# ProPrj.net
KiCad netlist of a schematic drawn in EasyEDA Pro
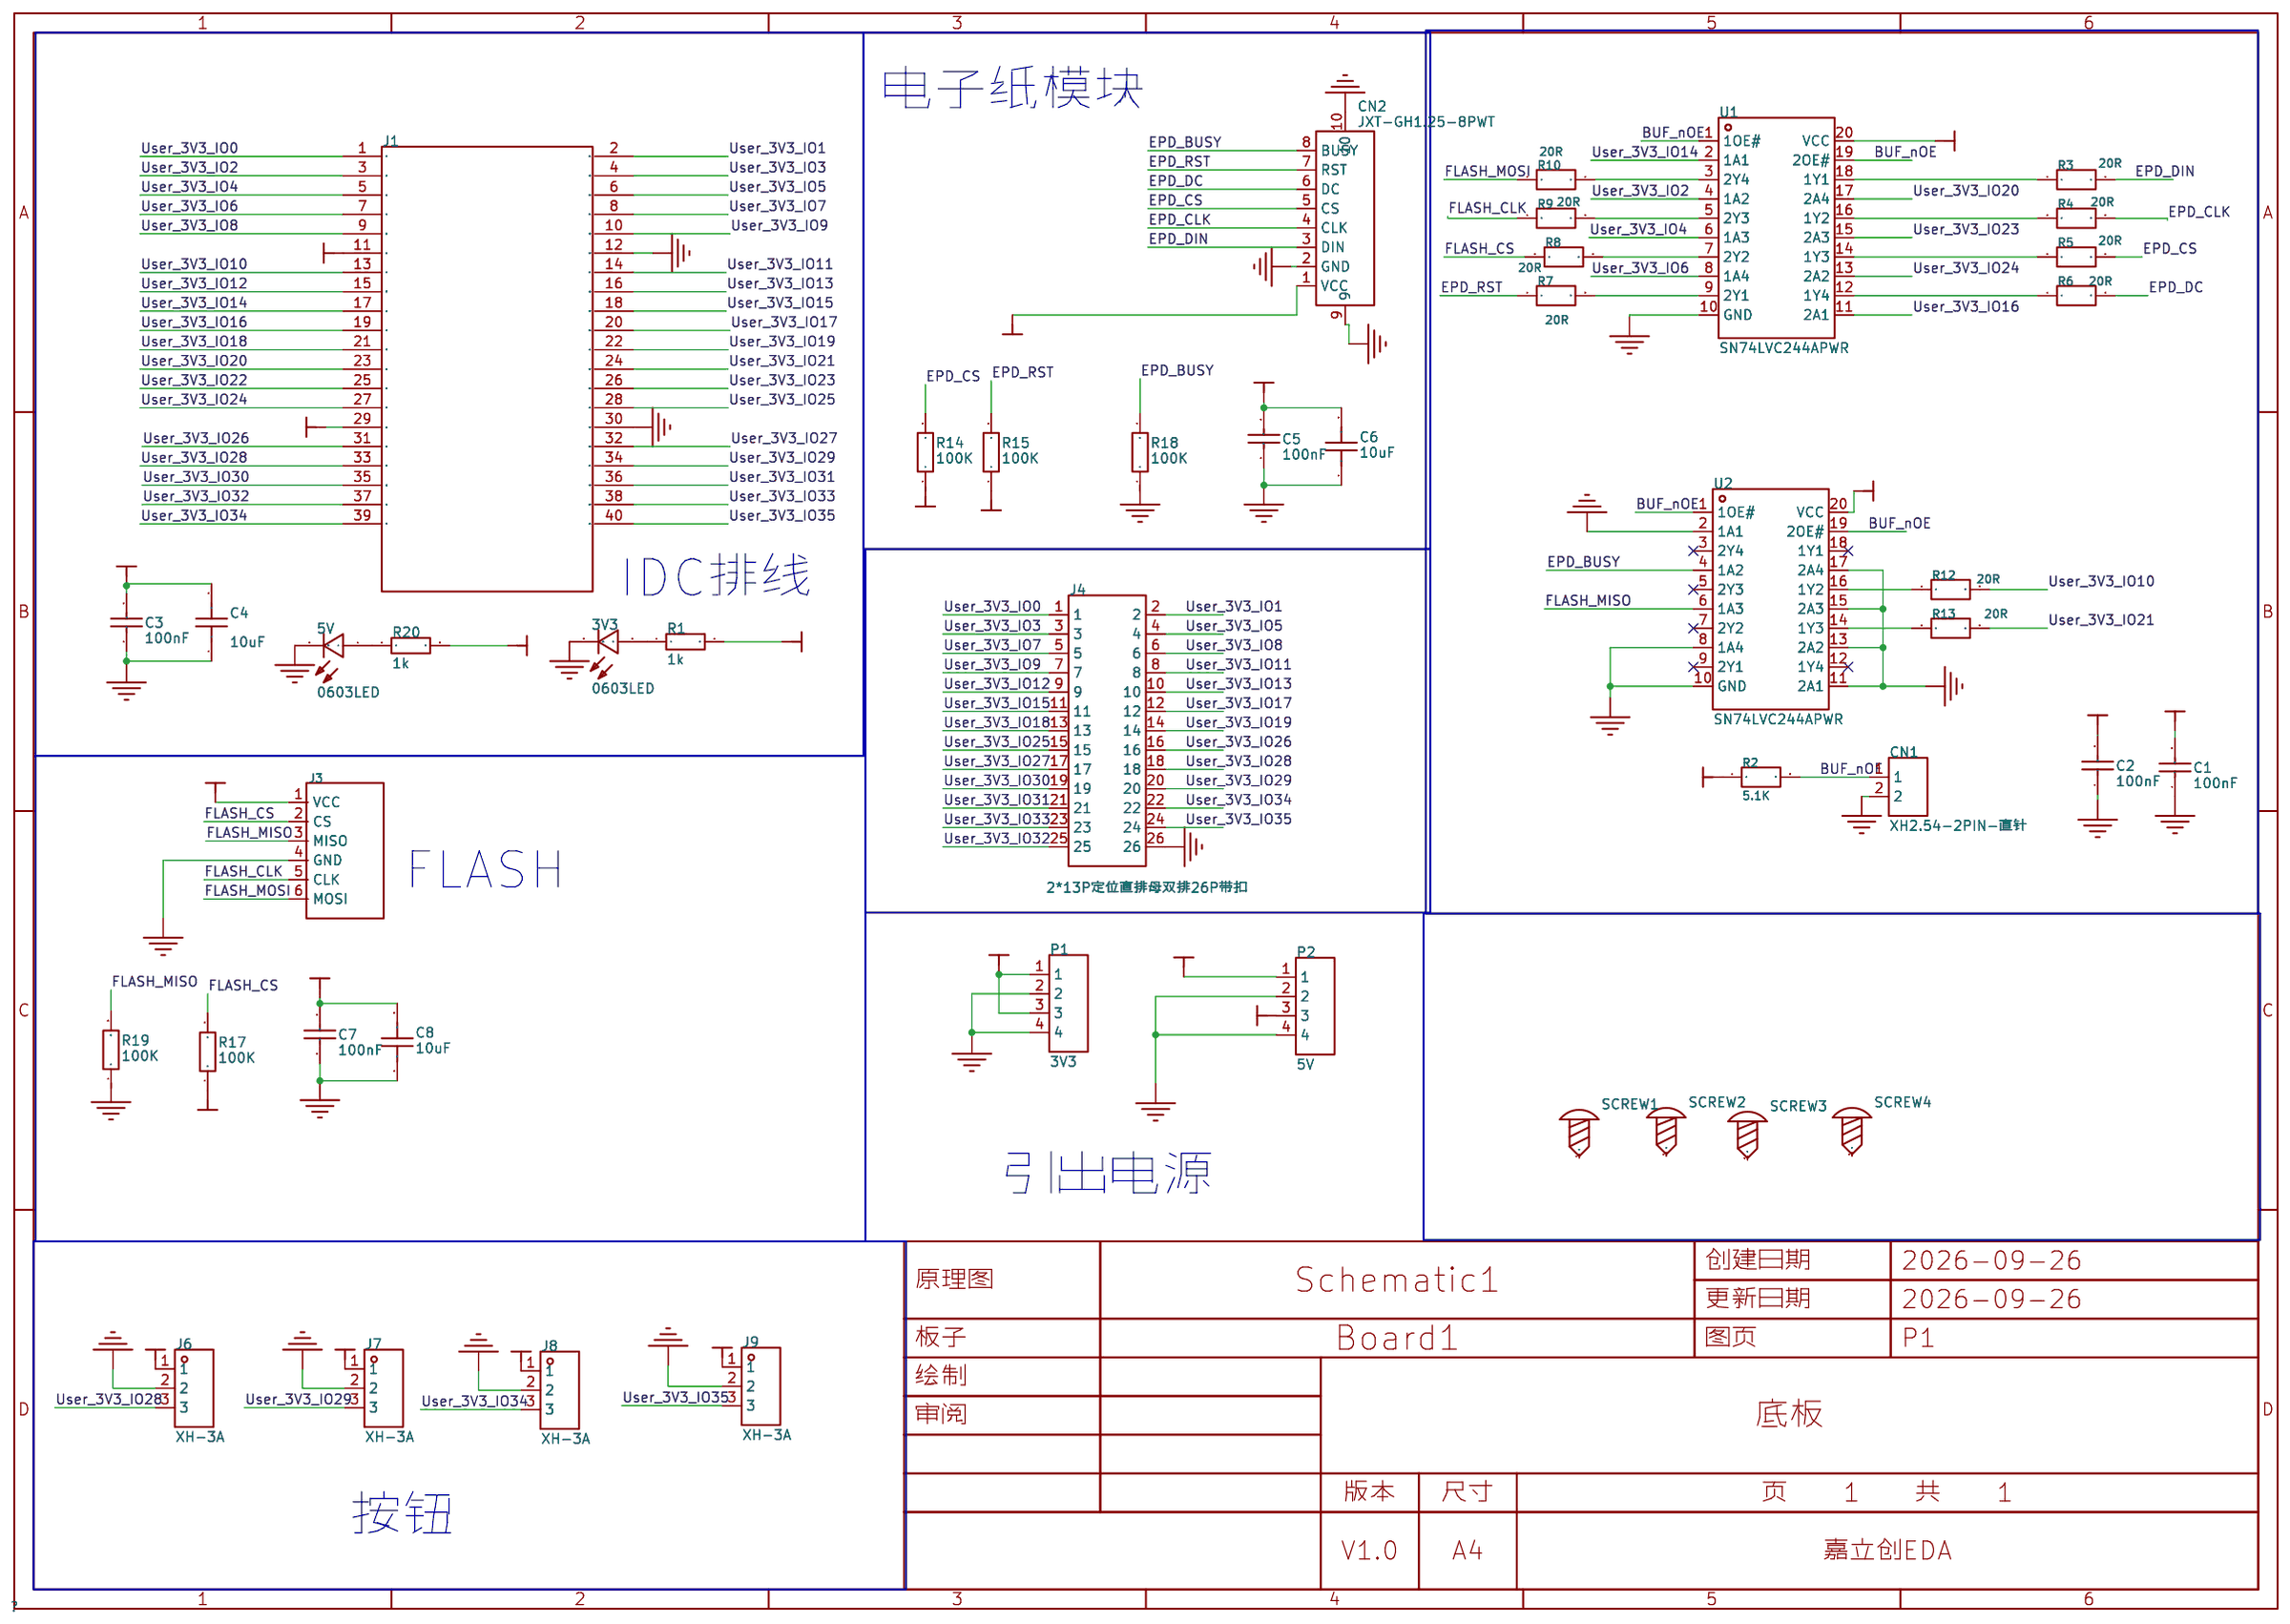
[diagram p0: schematic sheet]

(export (version "E")
  (design (tool "Eeschema 10.0.6"))
  (components
    (comp (ref "3V3")
      (value "0603LED")
      (footprint "easyedapro:LED0603-R-RD_RED")
      (libsource (lib "easyedapro") (part "0603LED"))
    )
    (comp (ref "5V")
      (value "0603LED")
      (footprint "easyedapro:LED0603-R-RD_RED")
      (libsource (lib "easyedapro") (part "0603LED"))
    )
    (comp (ref "C1")
      (value "100nF")
      (footprint "easyedapro:C0603")
      (fields
        (field (name "Manufacturer Part") "CL10A225KO8NNNC")
        (field (name "Manufacturer") "SAMSUNG(三星)")
      )
      (libsource (lib "easyedapro") (part "CL10A225KO8NNNC"))
    )
    (comp (ref "C2")
      (value "100nF")
      (footprint "easyedapro:C0603")
      (fields
        (field (name "Manufacturer Part") "CL10A225KO8NNNC")
        (field (name "Manufacturer") "SAMSUNG(三星)")
      )
      (libsource (lib "easyedapro") (part "CL10A225KO8NNNC"))
    )
    (comp (ref "C3")
      (value "100nF")
      (footprint "easyedapro:C0603")
      (fields
        (field (name "Manufacturer Part") "CL10A225KO8NNNC")
        (field (name "Manufacturer") "SAMSUNG(三星)")
      )
      (libsource (lib "easyedapro") (part "CL10A225KO8NNNC"))
    )
    (comp (ref "C4")
      (value "10uF")
      (footprint "easyedapro:C0805")
      (fields
        (field (name "Manufacturer Part") "GRM21BR61H106KE43L")
        (field (name "Manufacturer") "muRata(村田)")
      )
      (libsource (lib "easyedapro") (part "GRM21BR61H106KE43L"))
    )
    (comp (ref "C5")
      (value "100nF")
      (footprint "easyedapro:C0603")
      (fields
        (field (name "Manufacturer Part") "CL10A225KO8NNNC")
        (field (name "Manufacturer") "SAMSUNG(三星)")
      )
      (libsource (lib "easyedapro") (part "CL10A225KO8NNNC"))
    )
    (comp (ref "C6")
      (value "10uF")
      (footprint "easyedapro:C0805")
      (fields
        (field (name "Manufacturer Part") "GRM21BR61H106KE43L")
        (field (name "Manufacturer") "muRata(村田)")
      )
      (libsource (lib "easyedapro") (part "GRM21BR61H106KE43L"))
    )
    (comp (ref "C7")
      (value "100nF")
      (footprint "easyedapro:C0603")
      (fields
        (field (name "Manufacturer Part") "CL10A225KO8NNNC")
        (field (name "Manufacturer") "SAMSUNG(三星)")
      )
      (libsource (lib "easyedapro") (part "CL10A225KO8NNNC"))
    )
    (comp (ref "C8")
      (value "10uF")
      (footprint "easyedapro:C0805")
      (fields
        (field (name "Manufacturer Part") "GRM21BR61H106KE43L")
        (field (name "Manufacturer") "muRata(村田)")
      )
      (libsource (lib "easyedapro") (part "GRM21BR61H106KE43L"))
    )
    (comp (ref "CN1")
      (value "XH2.54-2PIN-直针")
      (footprint "easyedapro:CONN-TH_XH2.54-2P")
      (libsource (lib "easyedapro") (part "XH2.54-2PIN-直针"))
    )
    (comp (ref "CN2")
      (value "JXT-GH1.25-8PWT")
      (footprint "easyedapro:CONN-SMD_8P-P1.25_JXT-GH1.25-8PWT")
      (fields (field (name "Manufacturer") "JXTCONN(聚兴泰)"))
      (libsource (lib "easyedapro") (part "JXT-GH1.25-8PWT"))
    )
    (comp (ref "J1")
      (value "~")
      (footprint "easyedapro:IDC40P")
      (libsource (lib "easyedapro") (part "iDC40P"))
    )
    (comp (ref "J3")
      (value "X4611FV-06-C63D28")
      (footprint "easyedapro:HDR-TH_6P-P2.00-V-F")
      (fields (field (name "Manufacturer") "XKB Connection(中国星坤)"))
      (libsource (lib "easyedapro") (part "X4611FV-06-C63D28"))
    )
    (comp (ref "J4")
      (value "2*13P定位直排母双排26P带扣")
      (footprint "easyedapro:IDC-TH_26P-P2.54-V-M-R2-C13-S2.54")
      (libsource (lib "easyedapro") (part "2*13P定位直排母双排26P带扣"))
    )
    (comp (ref "J6")
      (value "XH-3A")
      (footprint "easyedapro:CONN-TH_3P-P2.50_C9900023074")
      (libsource (lib "easyedapro") (part "XH-3A_C9900023074"))
    )
    (comp (ref "J7")
      (value "XH-3A")
      (footprint "easyedapro:CONN-TH_3P-P2.50_C9900023074")
      (libsource (lib "easyedapro") (part "XH-3A_C9900023074"))
    )
    (comp (ref "J8")
      (value "XH-3A")
      (footprint "easyedapro:CONN-TH_3P-P2.50_C9900023074")
      (libsource (lib "easyedapro") (part "XH-3A_C9900023074"))
    )
    (comp (ref "J9")
      (value "XH-3A")
      (footprint "easyedapro:CONN-TH_3P-P2.50_C9900023074")
      (libsource (lib "easyedapro") (part "XH-3A_C9900023074"))
    )
    (comp (ref "P1")
      (value "3V3")
      (footprint "easyedapro:CONN-TH_4P-P2.50-XH2.54-4P")
      (libsource (lib "easyedapro") (part "XH2.54-4P"))
    )
    (comp (ref "P2")
      (value "5V")
      (footprint "easyedapro:CONN-TH_4P-P2.50-XH2.54-4P")
      (libsource (lib "easyedapro") (part "XH2.54-4P"))
    )
    (comp (ref "R1")
      (value "1k")
      (footprint "easyedapro:R0603")
      (description "电阻类型:厚膜电阻;阻值:3.3kΩ;精度:±1%;功率:100mW;工作电压:75V;温度系数:±100ppm/℃;")
      (fields
        (field (name "Manufacturer Part") "0603WAF3301T5E")
        (field (name "Manufacturer") "UNI-ROYAL(厚声)")
      )
      (libsource (lib "easyedapro") (part "0603WAF3301T5E"))
    )
    (comp (ref "R2")
      (value "5.1K")
      (footprint "easyedapro:R0603")
      (fields (field (name "Manufacturer Part") "FRQ0603F1302TS") (field (name "Manufacturer") "FOJAN(富捷)"))
      (libsource (lib "easyedapro") (part "FRQ0603F1302TS"))
    )
    (comp (ref "R3")
      (value "20R")
      (footprint "easyedapro:R0603")
      (fields (field (name "Manufacturer Part") "FRQ0603F1302TS") (field (name "Manufacturer") "FOJAN(富捷)"))
      (libsource (lib "easyedapro") (part "FRQ0603F1302TS"))
    )
    (comp (ref "R4")
      (value "20R")
      (footprint "easyedapro:R0603")
      (fields (field (name "Manufacturer Part") "FRQ0603F1302TS") (field (name "Manufacturer") "FOJAN(富捷)"))
      (libsource (lib "easyedapro") (part "FRQ0603F1302TS"))
    )
    (comp (ref "R5")
      (value "20R")
      (footprint "easyedapro:R0603")
      (fields (field (name "Manufacturer Part") "FRQ0603F1302TS") (field (name "Manufacturer") "FOJAN(富捷)"))
      (libsource (lib "easyedapro") (part "FRQ0603F1302TS"))
    )
    (comp (ref "R6")
      (value "20R")
      (footprint "easyedapro:R0603")
      (fields (field (name "Manufacturer Part") "FRQ0603F1302TS") (field (name "Manufacturer") "FOJAN(富捷)"))
      (libsource (lib "easyedapro") (part "FRQ0603F1302TS"))
    )
    (comp (ref "R7")
      (value "20R")
      (footprint "easyedapro:R0603")
      (fields (field (name "Manufacturer Part") "FRQ0603F1302TS") (field (name "Manufacturer") "FOJAN(富捷)"))
      (libsource (lib "easyedapro") (part "FRQ0603F1302TS"))
    )
    (comp (ref "R8")
      (value "20R")
      (footprint "easyedapro:R0603")
      (fields (field (name "Manufacturer Part") "FRQ0603F1302TS") (field (name "Manufacturer") "FOJAN(富捷)"))
      (libsource (lib "easyedapro") (part "FRQ0603F1302TS"))
    )
    (comp (ref "R9")
      (value "20R")
      (footprint "easyedapro:R0603")
      (fields (field (name "Manufacturer Part") "FRQ0603F1302TS") (field (name "Manufacturer") "FOJAN(富捷)"))
      (libsource (lib "easyedapro") (part "FRQ0603F1302TS"))
    )
    (comp (ref "R10")
      (value "20R")
      (footprint "easyedapro:R0603")
      (fields (field (name "Manufacturer Part") "FRQ0603F1302TS") (field (name "Manufacturer") "FOJAN(富捷)"))
      (libsource (lib "easyedapro") (part "FRQ0603F1302TS"))
    )
    (comp (ref "R12")
      (value "20R")
      (footprint "easyedapro:R0603")
      (fields (field (name "Manufacturer Part") "FRQ0603F1302TS") (field (name "Manufacturer") "FOJAN(富捷)"))
      (libsource (lib "easyedapro") (part "FRQ0603F1302TS"))
    )
    (comp (ref "R13")
      (value "20R")
      (footprint "easyedapro:R0603")
      (fields (field (name "Manufacturer Part") "FRQ0603F1302TS") (field (name "Manufacturer") "FOJAN(富捷)"))
      (libsource (lib "easyedapro") (part "FRQ0603F1302TS"))
    )
    (comp (ref "R14")
      (value "100K")
      (footprint "easyedapro:R0805")
      (fields
        (field (name "Manufacturer Part") "0805W8F3302T5E")
        (field (name "Manufacturer") "UNI-ROYAL(厚声)")
      )
      (libsource (lib "easyedapro") (part "0805W8F3302T5E"))
    )
    (comp (ref "R15")
      (value "100K")
      (footprint "easyedapro:R0805")
      (fields
        (field (name "Manufacturer Part") "0805W8F3302T5E")
        (field (name "Manufacturer") "UNI-ROYAL(厚声)")
      )
      (libsource (lib "easyedapro") (part "0805W8F3302T5E"))
    )
    (comp (ref "R17")
      (value "100K")
      (footprint "easyedapro:R0805")
      (fields
        (field (name "Manufacturer Part") "0805W8F3302T5E")
        (field (name "Manufacturer") "UNI-ROYAL(厚声)")
      )
      (libsource (lib "easyedapro") (part "0805W8F3302T5E"))
    )
    (comp (ref "R18")
      (value "100K")
      (footprint "easyedapro:R0805")
      (fields
        (field (name "Manufacturer Part") "0805W8F3302T5E")
        (field (name "Manufacturer") "UNI-ROYAL(厚声)")
      )
      (libsource (lib "easyedapro") (part "0805W8F3302T5E"))
    )
    (comp (ref "R19")
      (value "100K")
      (footprint "easyedapro:R0805")
      (fields
        (field (name "Manufacturer Part") "0805W8F3302T5E")
        (field (name "Manufacturer") "UNI-ROYAL(厚声)")
      )
      (libsource (lib "easyedapro") (part "0805W8F3302T5E"))
    )
    (comp (ref "R20")
      (value "1k")
      (footprint "easyedapro:R0603")
      (description "电阻类型:厚膜电阻;阻值:3.3kΩ;精度:±1%;功率:100mW;工作电压:75V;温度系数:±100ppm/℃;")
      (fields
        (field (name "Manufacturer Part") "0603WAF3301T5E")
        (field (name "Manufacturer") "UNI-ROYAL(厚声)")
      )
      (libsource (lib "easyedapro") (part "0603WAF3301T5E"))
    )
    (comp (ref "SCREW1")
      (value "~")
      (footprint "easyedapro:M3螺丝")
      (libsource (lib "easyedapro") (part "螺丝孔"))
    )
    (comp (ref "SCREW2")
      (value "~")
      (footprint "easyedapro:M3螺丝")
      (libsource (lib "easyedapro") (part "螺丝孔"))
    )
    (comp (ref "SCREW3")
      (value "~")
      (footprint "easyedapro:M3螺丝")
      (libsource (lib "easyedapro") (part "螺丝孔"))
    )
    (comp (ref "SCREW4")
      (value "~")
      (footprint "easyedapro:M3螺丝")
      (libsource (lib "easyedapro") (part "螺丝孔"))
    )
    (comp (ref "U1")
      (value "SN74LVC244APWR")
      (footprint "easyedapro:TSSOP-20_L6.5-W4.4-P0.65-LS6.4-BL")
      (fields (field (name "Manufacturer") "TI(德州仪器)"))
      (libsource (lib "easyedapro") (part "SN74LVC244APWR"))
    )
    (comp (ref "U2")
      (value "SN74LVC244APWR")
      (footprint "easyedapro:TSSOP-20_L6.5-W4.4-P0.65-LS6.4-BL")
      (fields (field (name "Manufacturer") "TI(德州仪器)"))
      (libsource (lib "easyedapro") (part "SN74LVC244APWR"))
    )
  )
  (nets
    (net (code "1") (name "/BUF_nOE") (class "Default")
      (node (ref "CN1") (pin "1") (pinfunction "1_1") (pintype "unspecified"))
      (node (ref "R2") (pin "2") (pinfunction "2_2") (pintype "unspecified"))
      (node (ref "U1") (pin "1") (pinfunction "1OE#_1") (pintype "unspecified"))
      (node (ref "U1") (pin "19") (pinfunction "2OE#_19") (pintype "unspecified"))
      (node (ref "U2") (pin "1") (pinfunction "1OE#_1") (pintype "unspecified"))
      (node (ref "U2") (pin "19") (pinfunction "2OE#_19") (pintype "unspecified"))
    )
    (net (code "2") (name "/EPD_BUSY") (class "Default")
      (node (ref "CN2") (pin "8") (pinfunction "BUSY_8") (pintype "unspecified"))
      (node (ref "R18") (pin "2") (pinfunction "2_2") (pintype "input"))
      (node (ref "U2") (pin "4") (pinfunction "1A2_4") (pintype "unspecified"))
    )
    (net (code "3") (name "/EPD_CLK") (class "Default")
      (node (ref "CN2") (pin "4") (pinfunction "CLK_4") (pintype "unspecified"))
      (node (ref "R4") (pin "2") (pinfunction "2_2") (pintype "unspecified"))
    )
    (net (code "4") (name "/EPD_CS") (class "Default")
      (node (ref "CN2") (pin "5") (pinfunction "CS_5") (pintype "unspecified"))
      (node (ref "R14") (pin "2") (pinfunction "2_2") (pintype "input"))
      (node (ref "R5") (pin "2") (pinfunction "2_2") (pintype "unspecified"))
    )
    (net (code "5") (name "/EPD_DC") (class "Default")
      (node (ref "CN2") (pin "6") (pinfunction "DC_6") (pintype "unspecified"))
      (node (ref "R6") (pin "2") (pinfunction "2_2") (pintype "unspecified"))
    )
    (net (code "6") (name "/EPD_DIN") (class "Default")
      (node (ref "CN2") (pin "3") (pinfunction "DIN_3") (pintype "unspecified"))
      (node (ref "R3") (pin "2") (pinfunction "2_2") (pintype "unspecified"))
    )
    (net (code "7") (name "/EPD_RST") (class "Default")
      (node (ref "CN2") (pin "7") (pinfunction "RST_7") (pintype "unspecified"))
      (node (ref "R15") (pin "2") (pinfunction "2_2") (pintype "input"))
      (node (ref "R7") (pin "1") (pinfunction "1_1") (pintype "unspecified"))
    )
    (net (code "8") (name "/FLASH_CLK") (class "Default")
      (node (ref "J3") (pin "5") (pinfunction "CLK_5") (pintype "unspecified"))
      (node (ref "R9") (pin "1") (pinfunction "1_1") (pintype "unspecified"))
    )
    (net (code "9") (name "/FLASH_CS") (class "Default")
      (node (ref "J3") (pin "2") (pinfunction "CS_2") (pintype "unspecified"))
      (node (ref "R17") (pin "2") (pinfunction "2_2") (pintype "input"))
      (node (ref "R8") (pin "1") (pinfunction "1_1") (pintype "unspecified"))
    )
    (net (code "10") (name "/FLASH_MISO") (class "Default")
      (node (ref "J3") (pin "3") (pinfunction "MISO_3") (pintype "unspecified"))
      (node (ref "R19") (pin "2") (pinfunction "2_2") (pintype "input"))
      (node (ref "U2") (pin "6") (pinfunction "1A3_6") (pintype "unspecified"))
    )
    (net (code "11") (name "/FLASH_MOSI") (class "Default")
      (node (ref "J3") (pin "6") (pinfunction "MOSI_6") (pintype "unspecified"))
      (node (ref "R10") (pin "1") (pinfunction "1_1") (pintype "unspecified"))
    )
    (net (code "12") (name "/User_3V3_IO0") (class "Default")
      (node (ref "J1") (pin "1") (pinfunction "1_1") (pintype "unspecified"))
      (node (ref "J4") (pin "1") (pinfunction "1_1") (pintype "unspecified"))
    )
    (net (code "13") (name "/User_3V3_IO1") (class "Default")
      (node (ref "J1") (pin "2") (pinfunction "21_2") (pintype "unspecified"))
      (node (ref "J4") (pin "2") (pinfunction "2_2") (pintype "unspecified"))
    )
    (net (code "14") (name "/User_3V3_IO2") (class "Default")
      (node (ref "J1") (pin "3") (pinfunction "2_3") (pintype "unspecified"))
      (node (ref "U1") (pin "4") (pinfunction "1A2_4") (pintype "unspecified"))
    )
    (net (code "15") (name "/User_3V3_IO3") (class "Default")
      (node (ref "J1") (pin "4") (pinfunction "22_4") (pintype "unspecified"))
      (node (ref "J4") (pin "3") (pinfunction "3_3") (pintype "unspecified"))
    )
    (net (code "16") (name "/User_3V3_IO4") (class "Default")
      (node (ref "J1") (pin "5") (pinfunction "3_5") (pintype "unspecified"))
      (node (ref "U1") (pin "6") (pinfunction "1A3_6") (pintype "unspecified"))
    )
    (net (code "17") (name "/User_3V3_IO5") (class "Default")
      (node (ref "J1") (pin "6") (pinfunction "23_6") (pintype "unspecified"))
      (node (ref "J4") (pin "4") (pinfunction "4_4") (pintype "unspecified"))
    )
    (net (code "18") (name "/User_3V3_IO6") (class "Default")
      (node (ref "J1") (pin "7") (pinfunction "4_7") (pintype "unspecified"))
      (node (ref "U1") (pin "8") (pinfunction "1A4_8") (pintype "unspecified"))
    )
    (net (code "19") (name "/User_3V3_IO7") (class "Default")
      (node (ref "J1") (pin "8") (pinfunction "24_8") (pintype "unspecified"))
      (node (ref "J4") (pin "5") (pinfunction "5_5") (pintype "unspecified"))
    )
    (net (code "20") (name "/User_3V3_IO8") (class "Default")
      (node (ref "J1") (pin "9") (pinfunction "5_9") (pintype "unspecified"))
      (node (ref "J4") (pin "6") (pinfunction "6_6") (pintype "unspecified"))
    )
    (net (code "21") (name "/User_3V3_IO9") (class "Default")
      (node (ref "J1") (pin "10") (pinfunction "25_10") (pintype "unspecified"))
      (node (ref "J4") (pin "7") (pinfunction "7_7") (pintype "unspecified"))
    )
    (net (code "22") (name "/User_3V3_IO10") (class "Default")
      (node (ref "J1") (pin "13") (pinfunction "7_13") (pintype "unspecified"))
      (node (ref "R12") (pin "2") (pinfunction "2_2") (pintype "unspecified"))
    )
    (net (code "23") (name "/User_3V3_IO11") (class "Default")
      (node (ref "J1") (pin "14") (pinfunction "27_14") (pintype "unspecified"))
      (node (ref "J4") (pin "8") (pinfunction "8_8") (pintype "unspecified"))
    )
    (net (code "24") (name "/User_3V3_IO12") (class "Default")
      (node (ref "J1") (pin "15") (pinfunction "8_15") (pintype "unspecified"))
      (node (ref "J4") (pin "9") (pinfunction "9_9") (pintype "unspecified"))
    )
    (net (code "25") (name "/User_3V3_IO13") (class "Default")
      (node (ref "J1") (pin "16") (pinfunction "28_16") (pintype "unspecified"))
      (node (ref "J4") (pin "10") (pinfunction "10_10") (pintype "unspecified"))
    )
    (net (code "26") (name "/User_3V3_IO14") (class "Default")
      (node (ref "J1") (pin "17") (pinfunction "9_17") (pintype "unspecified"))
      (node (ref "U1") (pin "2") (pinfunction "1A1_2") (pintype "unspecified"))
    )
    (net (code "27") (name "/User_3V3_IO15") (class "Default")
      (node (ref "J1") (pin "18") (pinfunction "29_18") (pintype "unspecified"))
      (node (ref "J4") (pin "11") (pinfunction "11_11") (pintype "unspecified"))
    )
    (net (code "28") (name "/User_3V3_IO16") (class "Default")
      (node (ref "J1") (pin "19") (pinfunction "10_19") (pintype "unspecified"))
      (node (ref "U1") (pin "11") (pinfunction "2A1_11") (pintype "unspecified"))
    )
    (net (code "29") (name "/User_3V3_IO17") (class "Default")
      (node (ref "J1") (pin "20") (pinfunction "30_20") (pintype "unspecified"))
      (node (ref "J4") (pin "12") (pinfunction "12_12") (pintype "unspecified"))
    )
    (net (code "30") (name "/User_3V3_IO18") (class "Default")
      (node (ref "J1") (pin "21") (pinfunction "11_21") (pintype "unspecified"))
      (node (ref "J4") (pin "13") (pinfunction "13_13") (pintype "unspecified"))
    )
    (net (code "31") (name "/User_3V3_IO19") (class "Default")
      (node (ref "J1") (pin "22") (pinfunction "31_22") (pintype "unspecified"))
      (node (ref "J4") (pin "14") (pinfunction "14_14") (pintype "unspecified"))
    )
    (net (code "32") (name "/User_3V3_IO20") (class "Default")
      (node (ref "J1") (pin "23") (pinfunction "12_23") (pintype "unspecified"))
      (node (ref "U1") (pin "17") (pinfunction "2A4_17") (pintype "unspecified"))
    )
    (net (code "33") (name "/User_3V3_IO21") (class "Default")
      (node (ref "J1") (pin "24") (pinfunction "32_24") (pintype "unspecified"))
      (node (ref "R13") (pin "2") (pinfunction "2_2") (pintype "unspecified"))
    )
    (net (code "34") (name "/User_3V3_IO22") (class "Default")
      (node (ref "J1") (pin "25") (pinfunction "13_25") (pintype "unspecified"))
    )
    (net (code "35") (name "/User_3V3_IO23") (class "Default")
      (node (ref "J1") (pin "26") (pinfunction "33_26") (pintype "unspecified"))
      (node (ref "U1") (pin "15") (pinfunction "2A3_15") (pintype "unspecified"))
    )
    (net (code "36") (name "/User_3V3_IO24") (class "Default")
      (node (ref "J1") (pin "27") (pinfunction "14_27") (pintype "unspecified"))
      (node (ref "U1") (pin "13") (pinfunction "2A2_13") (pintype "unspecified"))
    )
    (net (code "37") (name "/User_3V3_IO25") (class "Default")
      (node (ref "J1") (pin "28") (pinfunction "34_28") (pintype "unspecified"))
      (node (ref "J4") (pin "15") (pinfunction "15_15") (pintype "unspecified"))
    )
    (net (code "38") (name "/User_3V3_IO26") (class "Default")
      (node (ref "J1") (pin "31") (pinfunction "16_31") (pintype "unspecified"))
      (node (ref "J4") (pin "16") (pinfunction "16_16") (pintype "unspecified"))
    )
    (net (code "39") (name "/User_3V3_IO27") (class "Default")
      (node (ref "J1") (pin "32") (pinfunction "36_32") (pintype "unspecified"))
      (node (ref "J4") (pin "17") (pinfunction "17_17") (pintype "unspecified"))
    )
    (net (code "40") (name "/User_3V3_IO28") (class "Default")
      (node (ref "J1") (pin "33") (pinfunction "17_33") (pintype "unspecified"))
      (node (ref "J4") (pin "18") (pinfunction "18_18") (pintype "unspecified"))
      (node (ref "J6") (pin "3") (pinfunction "3_3") (pintype "unspecified"))
    )
    (net (code "41") (name "/User_3V3_IO29") (class "Default")
      (node (ref "J1") (pin "34") (pinfunction "37_34") (pintype "unspecified"))
      (node (ref "J4") (pin "20") (pinfunction "20_20") (pintype "unspecified"))
      (node (ref "J7") (pin "3") (pinfunction "3_3") (pintype "unspecified"))
    )
    (net (code "42") (name "/User_3V3_IO30") (class "Default")
      (node (ref "J1") (pin "35") (pinfunction "18_35") (pintype "unspecified"))
      (node (ref "J4") (pin "19") (pinfunction "19_19") (pintype "unspecified"))
    )
    (net (code "43") (name "/User_3V3_IO31") (class "Default")
      (node (ref "J1") (pin "36") (pinfunction "38_36") (pintype "unspecified"))
      (node (ref "J4") (pin "21") (pinfunction "21_21") (pintype "unspecified"))
    )
    (net (code "44") (name "/User_3V3_IO32") (class "Default")
      (node (ref "J1") (pin "37") (pinfunction "19_37") (pintype "unspecified"))
      (node (ref "J4") (pin "25") (pinfunction "25_25") (pintype "unspecified"))
    )
    (net (code "45") (name "/User_3V3_IO33") (class "Default")
      (node (ref "J1") (pin "38") (pinfunction "39_38") (pintype "unspecified"))
      (node (ref "J4") (pin "23") (pinfunction "23_23") (pintype "unspecified"))
    )
    (net (code "46") (name "/User_3V3_IO34") (class "Default")
      (node (ref "J1") (pin "39") (pinfunction "20_39") (pintype "unspecified"))
      (node (ref "J4") (pin "22") (pinfunction "22_22") (pintype "unspecified"))
      (node (ref "J8") (pin "3") (pinfunction "3_3") (pintype "unspecified"))
    )
    (net (code "47") (name "/User_3V3_IO35") (class "Default")
      (node (ref "J1") (pin "40") (pinfunction "40_40") (pintype "unspecified"))
      (node (ref "J4") (pin "24") (pinfunction "24_24") (pintype "unspecified"))
      (node (ref "J9") (pin "3") (pinfunction "3_3") (pintype "unspecified"))
    )
    (net (code "48") (name "3V3") (class "Default")
      (node (ref "C1") (pin "2") (pinfunction "2_2") (pintype "input"))
      (node (ref "C2") (pin "2") (pinfunction "2_2") (pintype "input"))
      (node (ref "C3") (pin "2") (pinfunction "2_2") (pintype "input"))
      (node (ref "C4") (pin "2") (pinfunction "2_2") (pintype "unspecified"))
      (node (ref "C5") (pin "2") (pinfunction "2_2") (pintype "input"))
      (node (ref "C6") (pin "2") (pinfunction "2_2") (pintype "unspecified"))
      (node (ref "C7") (pin "2") (pinfunction "2_2") (pintype "input"))
      (node (ref "C8") (pin "2") (pinfunction "2_2") (pintype "unspecified"))
      (node (ref "CN2") (pin "1") (pinfunction "VCC_1") (pintype "unspecified"))
      (node (ref "J1") (pin "29") (pinfunction "15_29") (pintype "unspecified"))
      (node (ref "J3") (pin "1") (pinfunction "VCC_1") (pintype "unspecified"))
      (node (ref "P1") (pin "1") (pinfunction "1_1") (pintype "unspecified"))
      (node (ref "P1") (pin "3") (pinfunction "3_3") (pintype "unspecified"))
      (node (ref "R1") (pin "2") (pinfunction "2_2") (pintype "input"))
      (node (ref "R14") (pin "1") (pinfunction "1_1") (pintype "input"))
      (node (ref "R15") (pin "1") (pinfunction "1_1") (pintype "input"))
      (node (ref "R17") (pin "1") (pinfunction "1_1") (pintype "input"))
      (node (ref "R2") (pin "1") (pinfunction "1_1") (pintype "unspecified"))
      (node (ref "U1") (pin "20") (pinfunction "VCC_20") (pintype "unspecified"))
      (node (ref "U2") (pin "20") (pinfunction "VCC_20") (pintype "unspecified"))
    )
    (net (code "49") (name "5V") (class "Default")
      (node (ref "J1") (pin "11") (pinfunction "6_11") (pintype "unspecified"))
      (node (ref "J6") (pin "1") (pinfunction "1_1") (pintype "unspecified"))
      (node (ref "J7") (pin "1") (pinfunction "1_1") (pintype "unspecified"))
      (node (ref "J8") (pin "1") (pinfunction "1_1") (pintype "unspecified"))
      (node (ref "J9") (pin "1") (pinfunction "1_1") (pintype "unspecified"))
      (node (ref "R20") (pin "2") (pinfunction "2_2") (pintype "input"))
    )
    (net (code "50") (name "GND") (class "Default")
      (node (ref "3V3") (pin "2") (pinfunction "C_2") (pintype "input"))
      (node (ref "5V") (pin "2") (pinfunction "C_2") (pintype "input"))
      (node (ref "C1") (pin "1") (pinfunction "1_1") (pintype "input"))
      (node (ref "C2") (pin "1") (pinfunction "1_1") (pintype "input"))
      (node (ref "C3") (pin "1") (pinfunction "1_1") (pintype "input"))
      (node (ref "C4") (pin "1") (pinfunction "1_1") (pintype "unspecified"))
      (node (ref "C5") (pin "1") (pinfunction "1_1") (pintype "input"))
      (node (ref "C6") (pin "1") (pinfunction "1_1") (pintype "unspecified"))
      (node (ref "C7") (pin "1") (pinfunction "1_1") (pintype "input"))
      (node (ref "C8") (pin "1") (pinfunction "1_1") (pintype "unspecified"))
      (node (ref "CN1") (pin "2") (pinfunction "2_2") (pintype "unspecified"))
      (node (ref "CN2") (pin "10") (pinfunction "10_10") (pintype "unspecified"))
      (node (ref "CN2") (pin "2") (pinfunction "GND_2") (pintype "unspecified"))
      (node (ref "CN2") (pin "9") (pinfunction "9_9") (pintype "unspecified"))
      (node (ref "J1") (pin "12") (pinfunction "26_12") (pintype "unspecified"))
      (node (ref "J1") (pin "30") (pinfunction "35_30") (pintype "unspecified"))
      (node (ref "J3") (pin "4") (pinfunction "GND_4") (pintype "unspecified"))
      (node (ref "J4") (pin "26") (pinfunction "26_26") (pintype "unspecified"))
      (node (ref "J6") (pin "2") (pinfunction "2_2") (pintype "unspecified"))
      (node (ref "J7") (pin "2") (pinfunction "2_2") (pintype "unspecified"))
      (node (ref "J8") (pin "2") (pinfunction "2_2") (pintype "unspecified"))
      (node (ref "J9") (pin "2") (pinfunction "2_2") (pintype "unspecified"))
      (node (ref "P1") (pin "2") (pinfunction "2_2") (pintype "unspecified"))
      (node (ref "P1") (pin "4") (pinfunction "4_4") (pintype "unspecified"))
      (node (ref "P2") (pin "2") (pinfunction "2_2") (pintype "unspecified"))
      (node (ref "R18") (pin "1") (pinfunction "1_1") (pintype "input"))
      (node (ref "R19") (pin "1") (pinfunction "1_1") (pintype "input"))
      (node (ref "U1") (pin "10") (pinfunction "GND_10") (pintype "unspecified"))
      (node (ref "U2") (pin "10") (pinfunction "GND_10") (pintype "unspecified"))
      (node (ref "U2") (pin "11") (pinfunction "2A1_11") (pintype "unspecified"))
      (node (ref "U2") (pin "13") (pinfunction "2A2_13") (pintype "unspecified"))
      (node (ref "U2") (pin "15") (pinfunction "2A3_15") (pintype "unspecified"))
      (node (ref "U2") (pin "17") (pinfunction "2A4_17") (pintype "unspecified"))
      (node (ref "U2") (pin "2") (pinfunction "1A1_2") (pintype "unspecified"))
      (node (ref "U2") (pin "8") (pinfunction "1A4_8") (pintype "unspecified"))
    )
    (net (code "51") (name "Net-(3V3-A)") (class "Default")
      (node (ref "3V3") (pin "1") (pinfunction "A_1") (pintype "input"))
      (node (ref "R1") (pin "1") (pinfunction "1_1") (pintype "input"))
    )
    (net (code "52") (name "Net-(5V-A)") (class "Default")
      (node (ref "5V") (pin "1") (pinfunction "A_1") (pintype "input"))
      (node (ref "R20") (pin "1") (pinfunction "1_1") (pintype "input"))
    )
    (net (code "53") (name "Net-(U1-1Y1)") (class "Default")
      (node (ref "R3") (pin "1") (pinfunction "1_1") (pintype "unspecified"))
      (node (ref "U1") (pin "18") (pinfunction "1Y1_18") (pintype "unspecified"))
    )
    (net (code "54") (name "Net-(U1-1Y2)") (class "Default")
      (node (ref "R4") (pin "1") (pinfunction "1_1") (pintype "unspecified"))
      (node (ref "U1") (pin "16") (pinfunction "1Y2_16") (pintype "unspecified"))
    )
    (net (code "55") (name "Net-(U1-1Y3)") (class "Default")
      (node (ref "R5") (pin "1") (pinfunction "1_1") (pintype "unspecified"))
      (node (ref "U1") (pin "14") (pinfunction "1Y3_14") (pintype "unspecified"))
    )
    (net (code "56") (name "Net-(U1-1Y4)") (class "Default")
      (node (ref "R6") (pin "1") (pinfunction "1_1") (pintype "unspecified"))
      (node (ref "U1") (pin "12") (pinfunction "1Y4_12") (pintype "unspecified"))
    )
    (net (code "57") (name "Net-(U1-2Y1)") (class "Default")
      (node (ref "R7") (pin "2") (pinfunction "2_2") (pintype "unspecified"))
      (node (ref "U1") (pin "9") (pinfunction "2Y1_9") (pintype "unspecified"))
    )
    (net (code "58") (name "Net-(U1-2Y2)") (class "Default")
      (node (ref "R8") (pin "2") (pinfunction "2_2") (pintype "unspecified"))
      (node (ref "U1") (pin "7") (pinfunction "2Y2_7") (pintype "unspecified"))
    )
    (net (code "59") (name "Net-(U1-2Y3)") (class "Default")
      (node (ref "R9") (pin "2") (pinfunction "2_2") (pintype "unspecified"))
      (node (ref "U1") (pin "5") (pinfunction "2Y3_5") (pintype "unspecified"))
    )
    (net (code "60") (name "Net-(U1-2Y4)") (class "Default")
      (node (ref "R10") (pin "2") (pinfunction "2_2") (pintype "unspecified"))
      (node (ref "U1") (pin "3") (pinfunction "2Y4_3") (pintype "unspecified"))
    )
    (net (code "61") (name "Net-(U2-1Y2)") (class "Default")
      (node (ref "R12") (pin "1") (pinfunction "1_1") (pintype "unspecified"))
      (node (ref "U2") (pin "16") (pinfunction "1Y2_16") (pintype "unspecified"))
    )
    (net (code "62") (name "Net-(U2-1Y3)") (class "Default")
      (node (ref "R13") (pin "1") (pinfunction "1_1") (pintype "unspecified"))
      (node (ref "U2") (pin "14") (pinfunction "1Y3_14") (pintype "unspecified"))
    )
    (net (code "63") (name "unconnected-(P2-Pad1)") (class "Default")
      (node (ref "P2") (pin "1") (pinfunction "1_1") (pintype "unspecified"))
    )
    (net (code "64") (name "unconnected-(P2-Pad3)") (class "Default")
      (node (ref "P2") (pin "3") (pinfunction "3_3") (pintype "unspecified"))
    )
    (net (code "65") (name "unconnected-(P2-Pad4)") (class "Default")
      (node (ref "P2") (pin "4") (pinfunction "4_4") (pintype "unspecified"))
    )
    (net (code "66") (name "unconnected-(SCREW1-Pad1)") (class "Default")
      (node (ref "SCREW1") (pin "1") (pinfunction "1_1") (pintype "input"))
    )
    (net (code "67") (name "unconnected-(SCREW2-Pad1)") (class "Default")
      (node (ref "SCREW2") (pin "1") (pinfunction "1_1") (pintype "input"))
    )
    (net (code "68") (name "unconnected-(SCREW3-Pad1)") (class "Default")
      (node (ref "SCREW3") (pin "1") (pinfunction "1_1") (pintype "input"))
    )
    (net (code "69") (name "unconnected-(SCREW4-Pad1)") (class "Default")
      (node (ref "SCREW4") (pin "1") (pinfunction "1_1") (pintype "input"))
    )
    (net (code "70") (name "unconnected-(U2-1Y1-Pad18)") (class "Default")
      (node (ref "U2") (pin "18") (pinfunction "1Y1_18") (pintype "unspecified+no_connect"))
    )
    (net (code "71") (name "unconnected-(U2-1Y4-Pad12)") (class "Default")
      (node (ref "U2") (pin "12") (pinfunction "1Y4_12") (pintype "unspecified+no_connect"))
    )
    (net (code "72") (name "unconnected-(U2-2Y1-Pad9)") (class "Default")
      (node (ref "U2") (pin "9") (pinfunction "2Y1_9") (pintype "unspecified+no_connect"))
    )
    (net (code "73") (name "unconnected-(U2-2Y2-Pad7)") (class "Default")
      (node (ref "U2") (pin "7") (pinfunction "2Y2_7") (pintype "unspecified+no_connect"))
    )
    (net (code "74") (name "unconnected-(U2-2Y3-Pad5)") (class "Default")
      (node (ref "U2") (pin "5") (pinfunction "2Y3_5") (pintype "unspecified+no_connect"))
    )
    (net (code "75") (name "unconnected-(U2-2Y4-Pad3)") (class "Default")
      (node (ref "U2") (pin "3") (pinfunction "2Y4_3") (pintype "unspecified+no_connect"))
    )
  )
)
